# STM-LF.net
KiCad netlist of a schematic drawn in Altium Designer
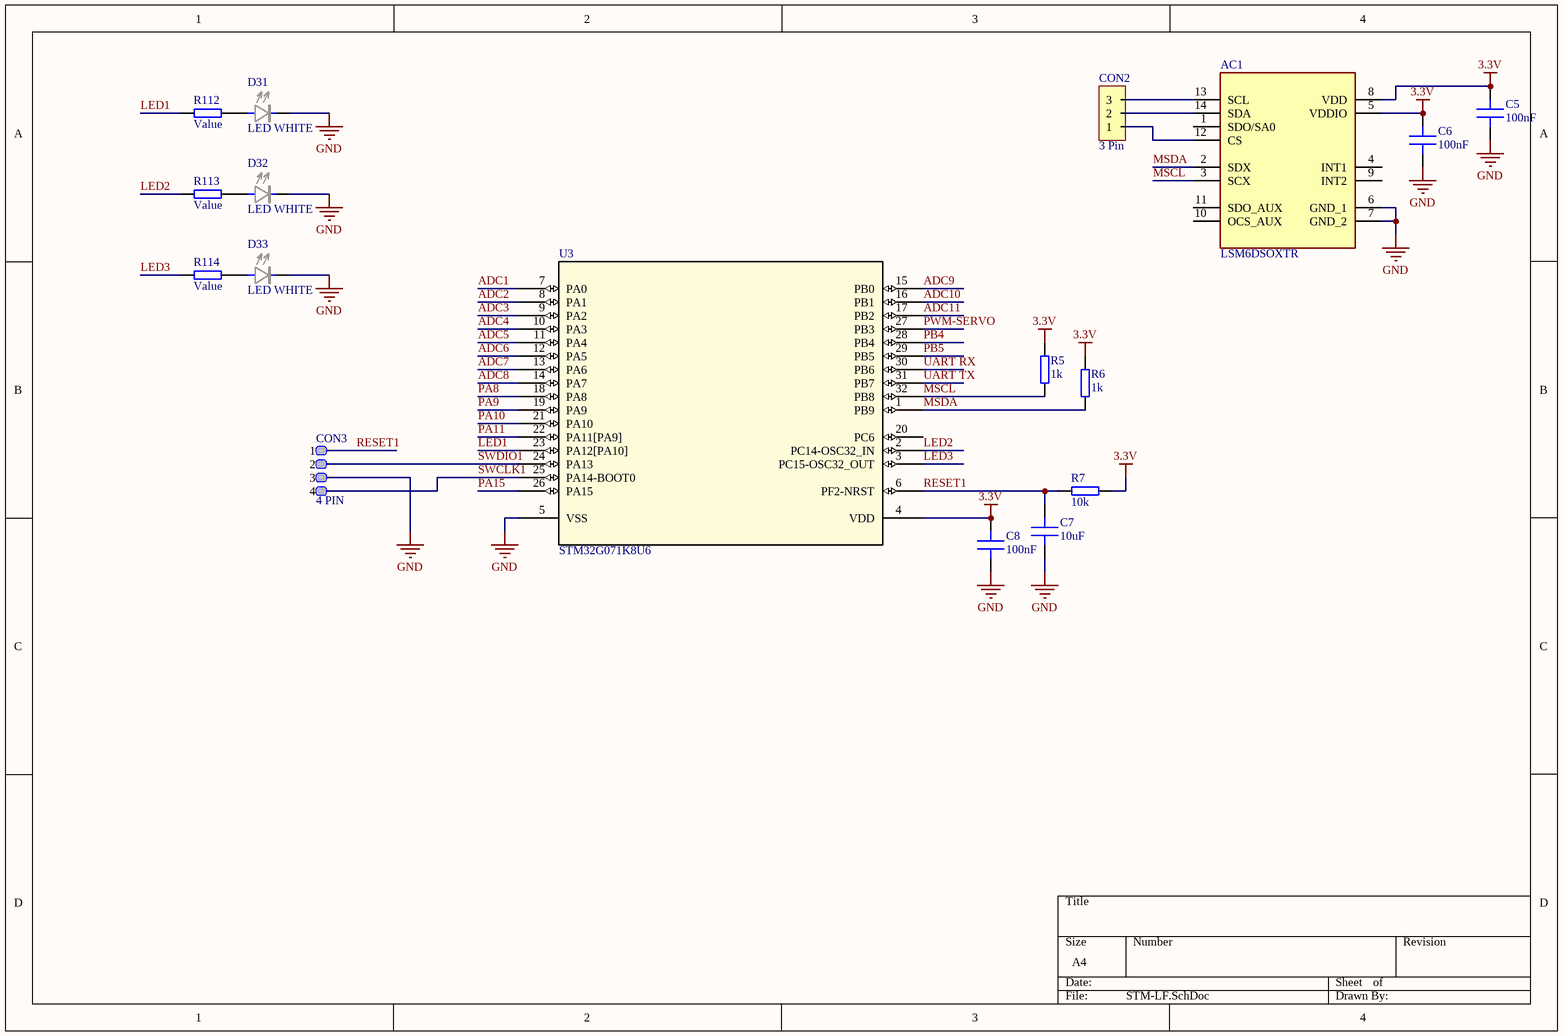
[diagram p0: STM-LF.SchDoc]

(export (version "E")
  (design (tool "Eeschema 10.0.6"))
  (components
    (comp (ref "AC1")
      (value "LSM6DSOXTR")
      (footprint "LGA-14_1")
      (description "Accelerometer")
      (fields (field (name "MOUSER PART NUMBER") "511-LSM6DSOXTR"))
      (libsource (lib "lib-all-components") (part "LSM6DSOXTR"))
    )
    (comp (ref "C5")
      (value "100nF")
      (footprint "C 0603")
      (description "MLCC Capacitor")
      (libsource (lib "Components") (part "Capacitor"))
    )
    (comp (ref "C6")
      (value "100nF")
      (footprint "C 0603")
      (description "MLCC Capacitor")
      (libsource (lib "Components") (part "Capacitor"))
    )
    (comp (ref "C7")
      (value "10uF")
      (footprint "C 0603")
      (description "MLCC Capacitor")
      (libsource (lib "Components") (part "Capacitor"))
    )
    (comp (ref "C8")
      (value "100nF")
      (footprint "C 0603")
      (description "MLCC Capacitor")
      (libsource (lib "Components") (part "Capacitor"))
    )
    (comp (ref "CON2")
      (value "3 Pin")
      (footprint "BM03B-SRSS-TB")
      (libsource (lib "Connectors") (part "3 Pin"))
    )
    (comp (ref "CON3")
      (value "4 PIN")
      (footprint "BM04B-SRSS-TB")
      (libsource (lib "Connectors") (part "4 PIN"))
    )
    (comp (ref "D31")
      (value "LED WHITE")
      (footprint "LED 0603 White")
      (libsource (lib "Components2") (part "LED WHITE"))
    )
    (comp (ref "D32")
      (value "LED WHITE")
      (footprint "LED 0603 White")
      (libsource (lib "Components2") (part "LED WHITE"))
    )
    (comp (ref "D33")
      (value "LED WHITE")
      (footprint "LED 0603 White")
      (libsource (lib "Components2") (part "LED WHITE"))
    )
    (comp (ref "R5")
      (value "1k")
      (footprint "R 0603")
      (description "General pourpouse resistor")
      (libsource (lib "Components") (part "Resistor"))
    )
    (comp (ref "R6")
      (value "1k")
      (footprint "R 0603")
      (description "General pourpouse resistor")
      (libsource (lib "Components") (part "Resistor"))
    )
    (comp (ref "R7")
      (value "10k")
      (footprint "R 0603")
      (description "General pourpouse resistor")
      (libsource (lib "Components") (part "Resistor"))
    )
    (comp (ref "R112")
      (value "Value")
      (footprint "R 0603")
      (description "General pourpouse resistor")
      (libsource (lib "Components") (part "Resistor"))
    )
    (comp (ref "R113")
      (value "Value")
      (footprint "R 0603")
      (description "General pourpouse resistor")
      (libsource (lib "Components") (part "Resistor"))
    )
    (comp (ref "R114")
      (value "Value")
      (footprint "R 0603")
      (description "General pourpouse resistor")
      (libsource (lib "Components") (part "Resistor"))
    )
    (comp (ref "U3")
      (value "STM32G071K8U6")
      (footprint "UFQFPN-32")
      (description "No Description Available")
      (fields (field (name "COPYRIGHT") "Copyright (C) 2024 Ultra Librarian. All rights reserved."))
      (libsource (lib "lib-all-components") (part "STM32G071K8U6"))
    )
  )
  (nets
    (net (code "1") (name "/ADC1") (class "Default")
      (node (ref "U3") (pin "7") (pinfunction "PA0_7") (pintype "bidirectional"))
    )
    (net (code "2") (name "/ADC2") (class "Default")
      (node (ref "U3") (pin "8") (pinfunction "PA1_8") (pintype "bidirectional"))
    )
    (net (code "3") (name "/ADC3") (class "Default")
      (node (ref "U3") (pin "9") (pinfunction "PA2_9") (pintype "bidirectional"))
    )
    (net (code "4") (name "/ADC4") (class "Default")
      (node (ref "U3") (pin "10") (pinfunction "PA3_10") (pintype "bidirectional"))
    )
    (net (code "5") (name "/ADC5") (class "Default")
      (node (ref "U3") (pin "11") (pinfunction "PA4_11") (pintype "bidirectional"))
    )
    (net (code "6") (name "/ADC6") (class "Default")
      (node (ref "U3") (pin "12") (pinfunction "PA5_12") (pintype "bidirectional"))
    )
    (net (code "7") (name "/ADC7") (class "Default")
      (node (ref "U3") (pin "13") (pinfunction "PA6_13") (pintype "bidirectional"))
    )
    (net (code "8") (name "/ADC8") (class "Default")
      (node (ref "U3") (pin "14") (pinfunction "PA7_14") (pintype "bidirectional"))
    )
    (net (code "9") (name "/ADC9") (class "Default")
      (node (ref "U3") (pin "15") (pinfunction "PB0_15") (pintype "bidirectional"))
    )
    (net (code "10") (name "/ADC10") (class "Default")
      (node (ref "U3") (pin "16") (pinfunction "PB1_16") (pintype "bidirectional"))
    )
    (net (code "11") (name "/ADC11") (class "Default")
      (node (ref "U3") (pin "17") (pinfunction "PB2_17") (pintype "bidirectional"))
    )
    (net (code "12") (name "/LED1") (class "Default")
      (node (ref "R112") (pin "1") (pinfunction "1_1") (pintype "passive"))
      (node (ref "U3") (pin "23") (pinfunction "PA12[PA10]_23") (pintype "bidirectional"))
    )
    (net (code "13") (name "/LED2") (class "Default")
      (node (ref "R113") (pin "1") (pinfunction "1_1") (pintype "passive"))
      (node (ref "U3") (pin "2") (pinfunction "PC14-OSC32_IN_2") (pintype "bidirectional"))
    )
    (net (code "14") (name "/LED3") (class "Default")
      (node (ref "R114") (pin "1") (pinfunction "1_1") (pintype "passive"))
      (node (ref "U3") (pin "3") (pinfunction "PC15-OSC32_OUT_3") (pintype "bidirectional"))
    )
    (net (code "15") (name "/MSCL") (class "Default")
      (node (ref "AC1") (pin "3") (pinfunction "SCX_3") (pintype "passive"))
      (node (ref "R5") (pin "2") (pinfunction "2_2") (pintype "passive"))
      (node (ref "U3") (pin "32") (pinfunction "PB8_32") (pintype "bidirectional"))
    )
    (net (code "16") (name "/MSDA") (class "Default")
      (node (ref "AC1") (pin "2") (pinfunction "SDX_2") (pintype "passive"))
      (node (ref "R6") (pin "2") (pinfunction "2_2") (pintype "passive"))
      (node (ref "U3") (pin "1") (pinfunction "PB9_1") (pintype "bidirectional"))
    )
    (net (code "17") (name "/PA8") (class "Default")
      (node (ref "U3") (pin "18") (pinfunction "PA8_18") (pintype "bidirectional"))
    )
    (net (code "18") (name "/PA9") (class "Default")
      (node (ref "U3") (pin "19") (pinfunction "PA9_19") (pintype "bidirectional"))
    )
    (net (code "19") (name "/PA10") (class "Default")
      (node (ref "U3") (pin "21") (pinfunction "PA10_21") (pintype "bidirectional"))
    )
    (net (code "20") (name "/PA11") (class "Default")
      (node (ref "U3") (pin "22") (pinfunction "PA11[PA9]_22") (pintype "bidirectional"))
    )
    (net (code "21") (name "/PA15") (class "Default")
      (node (ref "U3") (pin "26") (pinfunction "PA15_26") (pintype "bidirectional"))
    )
    (net (code "22") (name "/PB4") (class "Default")
      (node (ref "U3") (pin "28") (pinfunction "PB4_28") (pintype "bidirectional"))
    )
    (net (code "23") (name "/PB5") (class "Default")
      (node (ref "U3") (pin "29") (pinfunction "PB5_29") (pintype "bidirectional"))
    )
    (net (code "24") (name "/PWM-SERVO") (class "Default")
      (node (ref "U3") (pin "27") (pinfunction "PB3_27") (pintype "bidirectional"))
    )
    (net (code "25") (name "/RESET1") (class "Default")
      (node (ref "C7") (pin "2") (pinfunction "2_2") (pintype "passive"))
      (node (ref "CON3") (pin "1") (pinfunction "1_1") (pintype "passive"))
      (node (ref "R7") (pin "2") (pinfunction "2_2") (pintype "passive"))
      (node (ref "U3") (pin "6") (pinfunction "PF2-NRST_6") (pintype "bidirectional"))
    )
    (net (code "26") (name "/SWCLK1") (class "Default")
      (node (ref "CON3") (pin "4") (pinfunction "4_4") (pintype "passive"))
      (node (ref "U3") (pin "25") (pinfunction "PA14-BOOT0_25") (pintype "bidirectional"))
    )
    (net (code "27") (name "/SWDIO1") (class "Default")
      (node (ref "CON3") (pin "2") (pinfunction "2_2") (pintype "passive"))
      (node (ref "U3") (pin "24") (pinfunction "PA13_24") (pintype "bidirectional"))
    )
    (net (code "28") (name "/UART RX") (class "Default")
      (node (ref "U3") (pin "30") (pinfunction "PB6_30") (pintype "bidirectional"))
    )
    (net (code "29") (name "/UART TX") (class "Default")
      (node (ref "U3") (pin "31") (pinfunction "PB7_31") (pintype "bidirectional"))
    )
    (net (code "30") (name "3.3V") (class "Default")
      (node (ref "AC1") (pin "5") (pinfunction "VDDIO_5") (pintype "passive"))
      (node (ref "AC1") (pin "8") (pinfunction "VDD_8") (pintype "passive"))
      (node (ref "C5") (pin "2") (pinfunction "2_2") (pintype "passive"))
      (node (ref "C6") (pin "2") (pinfunction "2_2") (pintype "passive"))
      (node (ref "C8") (pin "2") (pinfunction "2_2") (pintype "passive"))
      (node (ref "R5") (pin "1") (pinfunction "1_1") (pintype "passive"))
      (node (ref "R6") (pin "1") (pinfunction "1_1") (pintype "passive"))
      (node (ref "R7") (pin "1") (pinfunction "1_1") (pintype "passive"))
      (node (ref "U3") (pin "4") (pinfunction "VDD_4") (pintype "power_in"))
    )
    (net (code "31") (name "GND") (class "Default")
      (node (ref "AC1") (pin "6") (pinfunction "GND_1_6") (pintype "passive"))
      (node (ref "AC1") (pin "7") (pinfunction "GND_2_7") (pintype "passive"))
      (node (ref "C5") (pin "1") (pinfunction "1_1") (pintype "passive"))
      (node (ref "C6") (pin "1") (pinfunction "1_1") (pintype "passive"))
      (node (ref "C7") (pin "1") (pinfunction "1_1") (pintype "passive"))
      (node (ref "C8") (pin "1") (pinfunction "1_1") (pintype "passive"))
      (node (ref "CON3") (pin "3") (pinfunction "3_3") (pintype "passive"))
      (node (ref "D31") (pin "2") (pinfunction "2_2") (pintype "passive"))
      (node (ref "D32") (pin "2") (pinfunction "2_2") (pintype "passive"))
      (node (ref "D33") (pin "2") (pinfunction "2_2") (pintype "passive"))
      (node (ref "U3") (pin "5") (pinfunction "VSS_5") (pintype "power_in"))
    )
    (net (code "32") (name "Net-(AC1-CS)") (class "Default")
      (node (ref "AC1") (pin "12") (pinfunction "CS_12") (pintype "passive"))
      (node (ref "CON2") (pin "1") (pinfunction "1_1") (pintype "passive"))
    )
    (net (code "33") (name "Net-(AC1-SCL)") (class "Default")
      (node (ref "AC1") (pin "13") (pinfunction "SCL_13") (pintype "passive"))
      (node (ref "CON2") (pin "3") (pinfunction "3_3") (pintype "passive"))
    )
    (net (code "34") (name "Net-(AC1-SDA)") (class "Default")
      (node (ref "AC1") (pin "14") (pinfunction "SDA_14") (pintype "passive"))
      (node (ref "CON2") (pin "2") (pinfunction "2_2") (pintype "passive"))
    )
    (net (code "35") (name "Net-(D31-Pad1)") (class "Default")
      (node (ref "D31") (pin "1") (pinfunction "1_1") (pintype "passive"))
      (node (ref "R112") (pin "2") (pinfunction "2_2") (pintype "passive"))
    )
    (net (code "36") (name "Net-(D32-Pad1)") (class "Default")
      (node (ref "D32") (pin "1") (pinfunction "1_1") (pintype "passive"))
      (node (ref "R113") (pin "2") (pinfunction "2_2") (pintype "passive"))
    )
    (net (code "37") (name "Net-(D33-Pad1)") (class "Default")
      (node (ref "D33") (pin "1") (pinfunction "1_1") (pintype "passive"))
      (node (ref "R114") (pin "2") (pinfunction "2_2") (pintype "passive"))
    )
    (net (code "38") (name "unconnected-(AC1-INT1-Pad4)") (class "Default")
      (node (ref "AC1") (pin "4") (pinfunction "INT1_4") (pintype "passive"))
    )
    (net (code "39") (name "unconnected-(AC1-INT2-Pad9)") (class "Default")
      (node (ref "AC1") (pin "9") (pinfunction "INT2_9") (pintype "passive"))
    )
    (net (code "40") (name "unconnected-(AC1-OCS_AUX-Pad10)") (class "Default")
      (node (ref "AC1") (pin "10") (pinfunction "OCS_AUX_10") (pintype "passive"))
    )
    (net (code "41") (name "unconnected-(AC1-SDO_AUX-Pad11)") (class "Default")
      (node (ref "AC1") (pin "11") (pinfunction "SDO_AUX_11") (pintype "passive"))
    )
    (net (code "42") (name "unconnected-(AC1-SDO{slash}SA0-Pad1)") (class "Default")
      (node (ref "AC1") (pin "1") (pinfunction "SDO/SA0_1") (pintype "passive"))
    )
    (net (code "43") (name "unconnected-(U3-PC6-Pad20)") (class "Default")
      (node (ref "U3") (pin "20") (pinfunction "PC6_20") (pintype "bidirectional"))
    )
  )
)
